# number1.net
KiCad netlist of a schematic drawn in Altium Designer
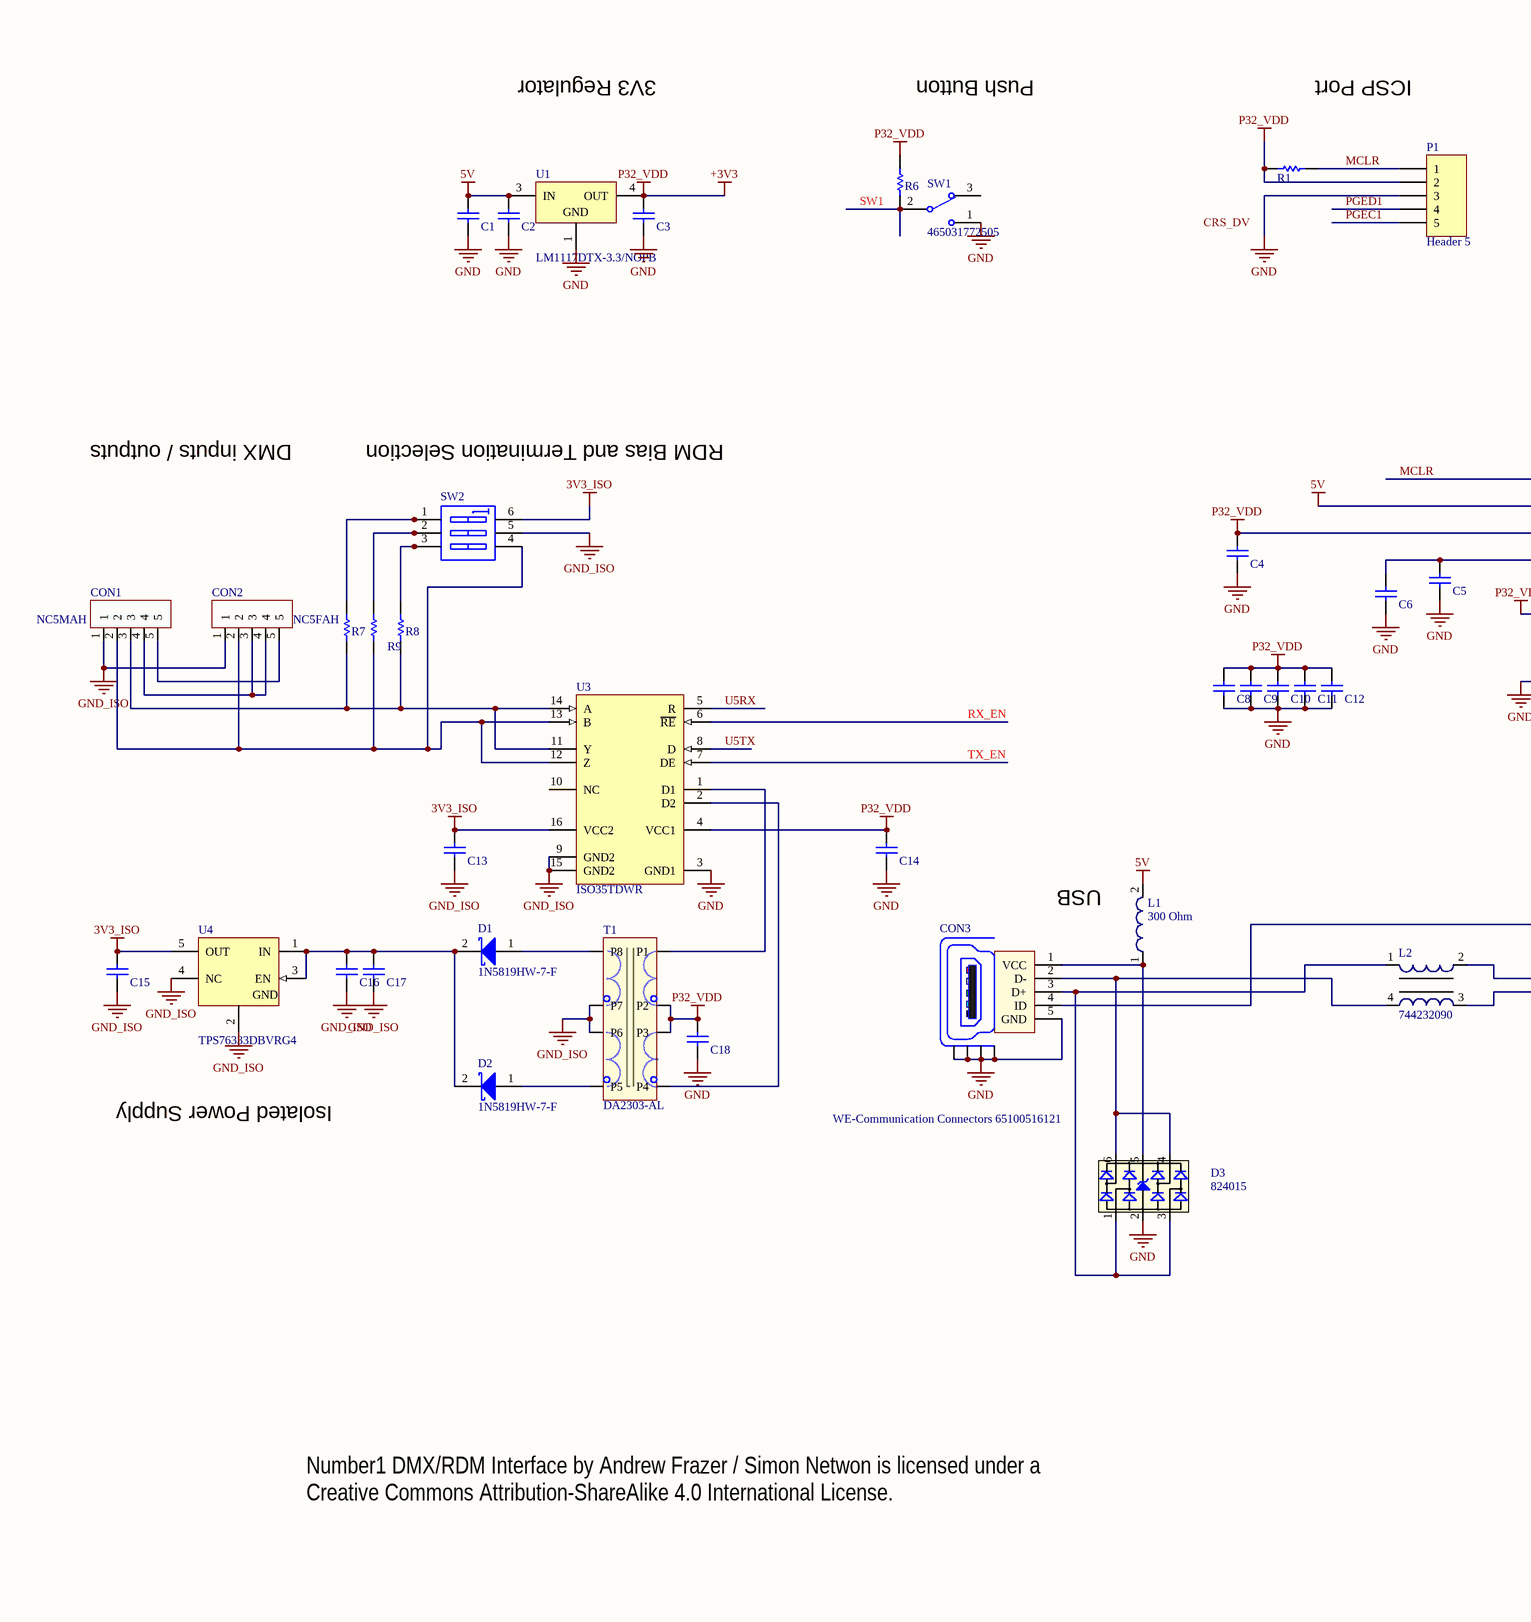
[diagram p0: number1.SchDoc, left]
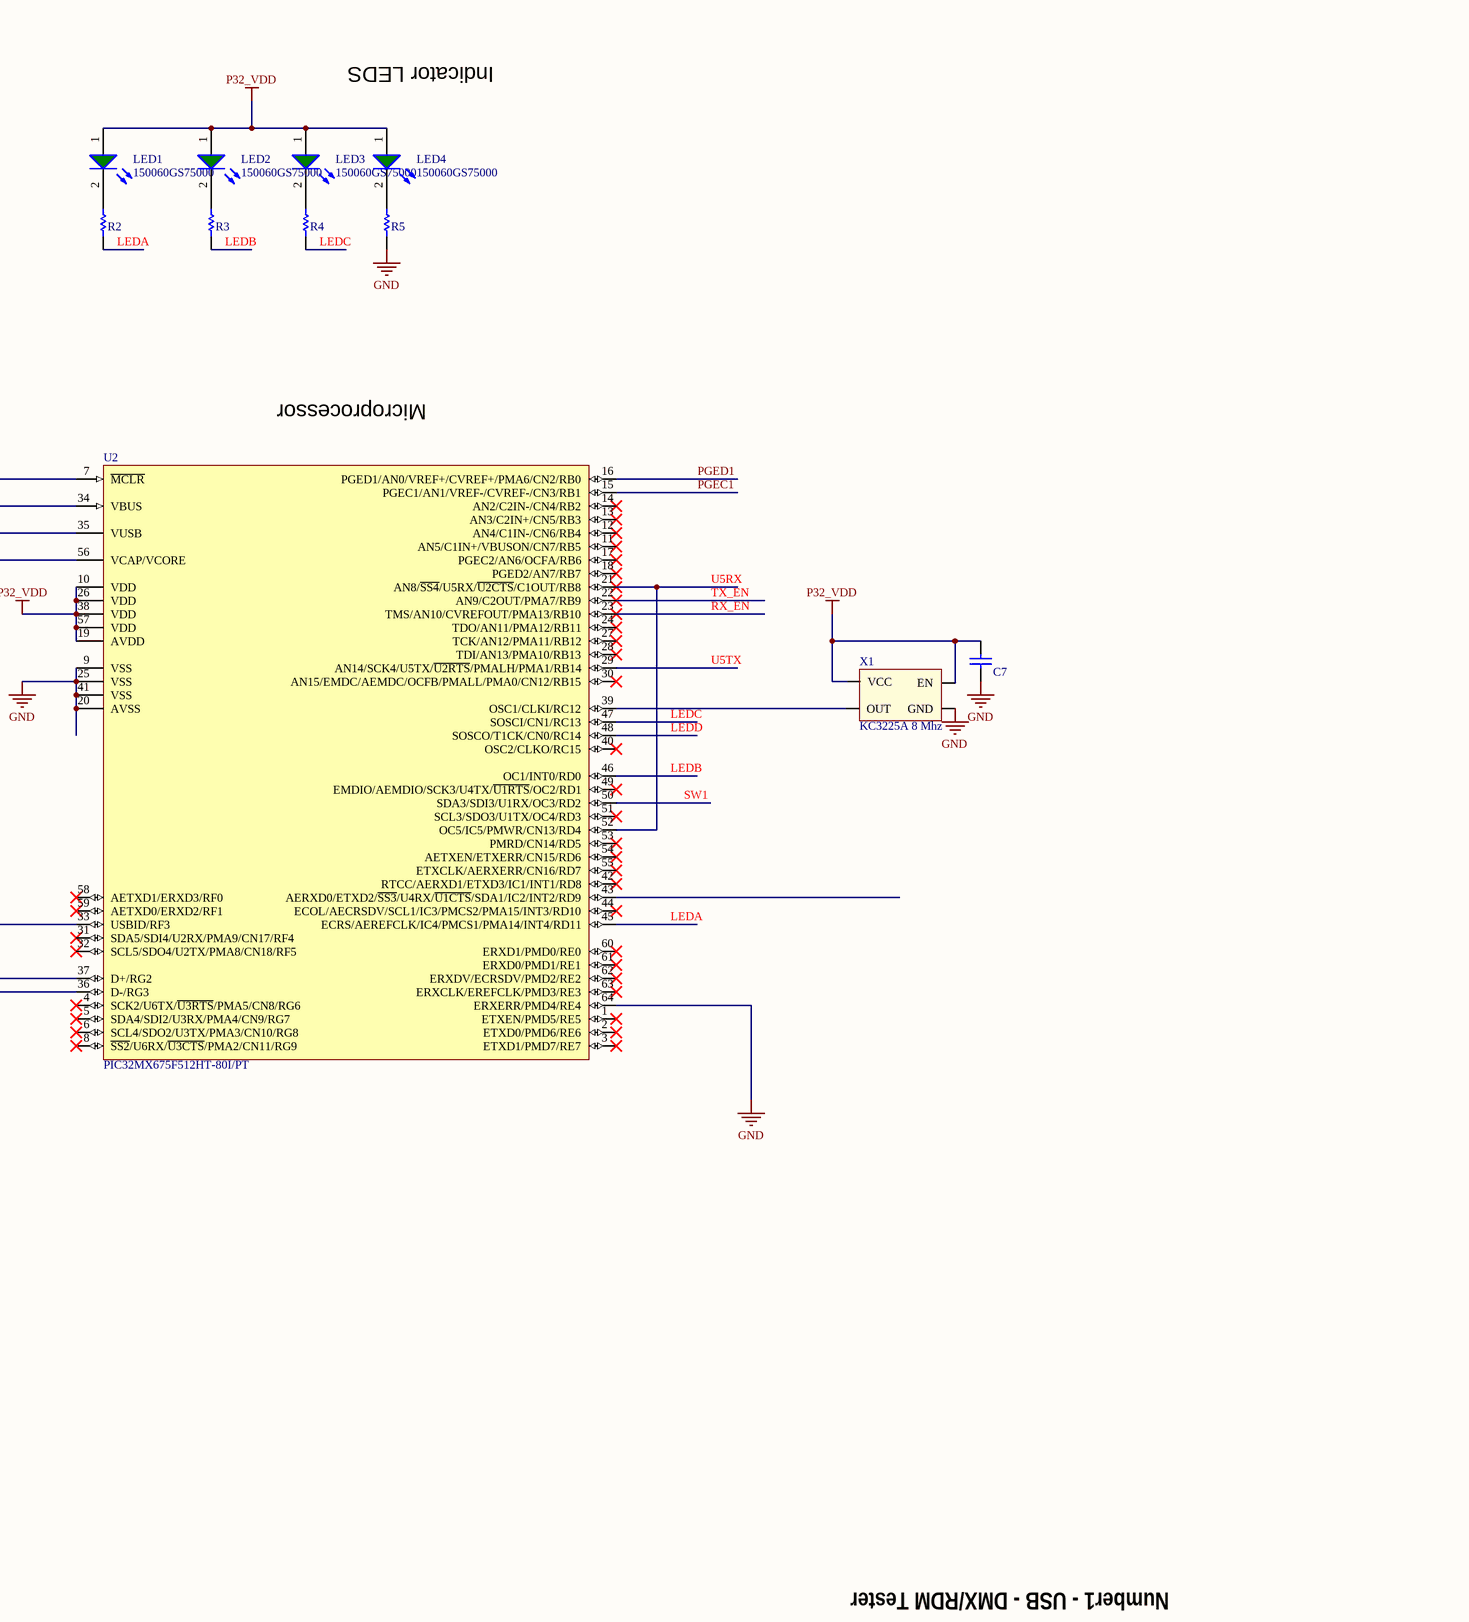
[diagram p1: number1.SchDoc, right]

(export (version "E")
  (design (tool "Eeschema 10.0.6"))
  (components
    (comp (ref "C1")
      (value "CAP 10.0uF 50V 0805(2012)")
      (footprint "CAPC0805(2012)145_M")
      (description "CAP 10uF 50V ±20% 0805 (2012 Metric) Thickness 1.45mm SMD")
      (fields (field (name "TOLERANCE") "±20%"))
      (libsource (lib "Altium Content Vault") (part "CMP-1036-04901-1"))
    )
    (comp (ref "C2")
      (value "CAP 100nF 50V 0402(1005)")
      (footprint "CAPC0402(1005)60_M")
      (description "CAP 100nF 50V ±10% 0402 (1005 Metric) Thickness 0.6mm SMD")
      (fields (field (name "TOLERANCE") "±10%"))
      (libsource (lib "Altium Content Vault") (part "CAP"))
    )
    (comp (ref "C3")
      (value "CAP 100nF 50V 0402(1005)")
      (footprint "CAPC0402(1005)60_M")
      (description "CAP 100nF 50V ±10% 0402 (1005 Metric) Thickness 0.6mm SMD")
      (fields (field (name "TOLERANCE") "±10%"))
      (libsource (lib "Altium Content Vault") (part "CAP"))
    )
    (comp (ref "C4")
      (value "CAP 100nF 50V 0402(1005)")
      (footprint "CAPC0402(1005)60_M")
      (description "CAP 100nF 50V ±10% 0402 (1005 Metric) Thickness 0.6mm SMD")
      (fields (field (name "TOLERANCE") "±10%"))
      (libsource (lib "Altium Content Vault") (part "CMP-1034-02077-1"))
    )
    (comp (ref "C5")
      (value "CAP 10.0uF 50V 0805(2012)")
      (footprint "CAPC0805(2012)145_M")
      (description "CAP 10uF 50V ±20% 0805 (2012 Metric) Thickness 1.45mm SMD")
      (fields (field (name "TOLERANCE") "±20%"))
      (libsource (lib "Altium Content Vault") (part "CMP-1036-04901-1"))
    )
    (comp (ref "C6")
      (value "CAP 100nF 50V 0402(1005)")
      (footprint "CAPC0402(1005)60_M")
      (description "CAP 100nF 50V ±10% 0402 (1005 Metric) Thickness 0.6mm SMD")
      (fields (field (name "TOLERANCE") "±10%"))
      (libsource (lib "Altium Content Vault") (part "CAP"))
    )
    (comp (ref "C7")
      (value "CAP 100nF 50V 0402(1005)")
      (footprint "CAPC0402(1005)60_M")
      (description "CAP 100nF 50V ±10% 0402 (1005 Metric) Thickness 0.6mm SMD")
      (fields (field (name "TOLERANCE") "±10%"))
      (libsource (lib "Altium Content Vault") (part "CMP-1034-02077-1"))
    )
    (comp (ref "C8")
      (value "CAP 100nF 50V 0402(1005)")
      (footprint "CAPC0402(1005)60_M")
      (description "CAP 100nF 50V ±10% 0402 (1005 Metric) Thickness 0.6mm SMD")
      (fields (field (name "TOLERANCE") "±10%"))
      (libsource (lib "Altium Content Vault") (part "CAP"))
    )
    (comp (ref "C9")
      (value "CAP 100nF 50V 0402(1005)")
      (footprint "CAPC0402(1005)60_M")
      (description "CAP 100nF 50V ±10% 0402 (1005 Metric) Thickness 0.6mm SMD")
      (fields (field (name "TOLERANCE") "±10%"))
      (libsource (lib "Altium Content Vault") (part "CAP"))
    )
    (comp (ref "C10")
      (value "CAP 100nF 50V 0402(1005)")
      (footprint "CAPC0402(1005)60_M")
      (description "CAP 100nF 50V ±10% 0402 (1005 Metric) Thickness 0.6mm SMD")
      (fields (field (name "TOLERANCE") "±10%"))
      (libsource (lib "Altium Content Vault") (part "CAP"))
    )
    (comp (ref "C11")
      (value "CAP 100nF 50V 0402(1005)")
      (footprint "CAPC0402(1005)60_M")
      (description "CAP 100nF 50V ±10% 0402 (1005 Metric) Thickness 0.6mm SMD")
      (fields (field (name "TOLERANCE") "±10%"))
      (libsource (lib "Altium Content Vault") (part "CAP"))
    )
    (comp (ref "C12")
      (value "CAP 100nF 50V 0402(1005)")
      (footprint "CAPC0402(1005)60_M")
      (description "CAP 100nF 50V ±10% 0402 (1005 Metric) Thickness 0.6mm SMD")
      (fields (field (name "TOLERANCE") "±10%"))
      (libsource (lib "Altium Content Vault") (part "CAP"))
    )
    (comp (ref "C13")
      (value "CAP 100nF 50V 0402(1005)")
      (footprint "CAPC0402(1005)60_M")
      (description "CAP 100nF 50V ±10% 0402 (1005 Metric) Thickness 0.6mm SMD")
      (fields (field (name "TOLERANCE") "±10%"))
      (libsource (lib "Altium Content Vault") (part "CMP-1034-02077-1"))
    )
    (comp (ref "C14")
      (value "CAP 100nF 50V 0402(1005)")
      (footprint "CAPC0402(1005)60_M")
      (description "CAP 100nF 50V ±10% 0402 (1005 Metric) Thickness 0.6mm SMD")
      (fields (field (name "TOLERANCE") "±10%"))
      (libsource (lib "Altium Content Vault") (part "CMP-1034-02077-1"))
    )
    (comp (ref "C15")
      (value "CAP 10.0uF 50V 0805(2012)")
      (footprint "CAPC0805(2012)145_M")
      (description "CAP 10uF 50V ±20% 0805 (2012 Metric) Thickness 1.45mm SMD")
      (fields (field (name "TOLERANCE") "±20%"))
      (libsource (lib "Altium Content Vault") (part "CMP-1036-04901-1"))
    )
    (comp (ref "C16")
      (value "CAP 100nF 50V 0402(1005)")
      (footprint "CAPC0402(1005)60_M")
      (description "CAP 100nF 50V ±10% 0402 (1005 Metric) Thickness 0.6mm SMD")
      (fields (field (name "TOLERANCE") "±10%"))
      (libsource (lib "Altium Content Vault") (part "CMP-1034-02077-1"))
    )
    (comp (ref "C17")
      (value "CAP 10.0uF 50V 0805(2012)")
      (footprint "CAPC0805(2012)145_M")
      (description "CAP 10uF 50V ±20% 0805 (2012 Metric) Thickness 1.45mm SMD")
      (fields (field (name "TOLERANCE") "±20%"))
      (libsource (lib "Altium Content Vault") (part "CMP-1036-04901-1"))
    )
    (comp (ref "C18")
      (value "CAP 10.0uF 50V 0805(2012)")
      (footprint "CAPC0805(2012)145_M")
      (description "CAP 10uF 50V ±20% 0805 (2012 Metric) Thickness 1.45mm SMD")
      (fields (field (name "TOLERANCE") "±20%"))
      (libsource (lib "Altium Content Vault") (part "CMP-1036-04901-1"))
    )
    (comp (ref "CON1") (value "NC5MAH") (footprint "NC5MAH") (libsource (lib "neutrik") (part "NC5MAH")))
    (comp (ref "CON2") (value "NC5FAH") (footprint "NC5FAH") (libsource (lib "neutrik") (part "NC5FAH")))
    (comp (ref "CON3")
      (value "WE-Communication Connectors 65100516121")
      (footprint "65100516121")
      (description "WR-COM Mini USB SMT Type B 5 Contacts")
      (fields
        (field (name "MANUFACTURER") "Würth Elektronik eiSos GmbH")
        (field (name "PARTNO") "65100516121")
        (field (name "CREATED BY") "Karrer Zheng")
      )
      (libsource (lib "65100516121") (part "WE-Communication Connectors 65100516121"))
    )
    (comp (ref "D1")
      (value "1N5819HW-7-F")
      (footprint "DIOD-SOD-123-2_V")
      (fields (field (name "MANUFACTURER") "Diodes Inc"))
      (libsource (lib "Altium Content Vault") (part "DIOD-DSKY-A1K2-2"))
    )
    (comp (ref "D2")
      (value "1N5819HW-7-F")
      (footprint "DIOD-SOD-123-2_V")
      (fields (field (name "MANUFACTURER") "Diodes Inc"))
      (libsource (lib "Altium Content Vault") (part "DIOD-DSKY-A1K2-2"))
    )
    (comp (ref "D3")
      (value "824015")
      (footprint "SOT23_6L")
      (description "TVS Diode WE-TVS-HS, VRWM=5V")
      (fields
        (field (name "MANUFACTURER") "W黵th Elektronik eiSos GmbH")
        (field (name "CREATED BY") "Christin Zierenner")
      )
      (libsource (lib "WE-TVSHighSpeed") (part "WE-TVS-HS,SOT23-6L, 824015"))
    )
    (comp (ref "L1")
      (value "300 Ohm")
      (footprint "SMD 0603")
      (description "SMD EMI Suppression Ferrite Beads WE-CBF, Z= 300 Ohm")
      (fields
        (field (name "PARTNO") "742792641")
        (field (name "MANUFACTURER") "Würth Elektronik eiSos GmbH")
        (field (name "CREATED BY") "Christin Zierenner")
      )
      (libsource (lib "WE-CBF") (part "WE-CBF 0603, 742792641"))
    )
    (comp (ref "L2")
      (value "744232090")
      (footprint "WE-CNSW, 1206")
      (description "SMD Common Mode Noise Suppressor WE-CNSW,  Z= 90 Ohm")
      (fields
        (field (name "MANUFACTURER") "Würth Elektronik eiSos GmbH")
        (field (name "CREATED BY") "Christin Zierenner")
      )
      (libsource (lib "WE-CNSW") (part "WE-CNSW 1206, 744232090"))
    )
    (comp (ref "LED1")
      (value "150060GS75000")
      (footprint "LED_0603_Green")
      (description "SMD mono-color Chip LED, WL-SMCW, Green")
      (fields
        (field (name "MANUFACTURER") "W黵th Elektronik eiSos GmbH")
        (field (name "CREATED BY") "Christin Otto")
      )
      (libsource (lib "WL-SMCW") (part "WL-SMCW 0603  150060GS75000"))
    )
    (comp (ref "LED2")
      (value "150060GS75000")
      (footprint "LED_0603_Green")
      (description "SMD mono-color Chip LED, WL-SMCW, Green")
      (fields
        (field (name "MANUFACTURER") "W黵th Elektronik eiSos GmbH")
        (field (name "CREATED BY") "Christin Otto")
      )
      (libsource (lib "WL-SMCW") (part "WL-SMCW 0603  150060GS75000"))
    )
    (comp (ref "LED3")
      (value "150060GS75000")
      (footprint "LED_0603_Green")
      (description "SMD mono-color Chip LED, WL-SMCW, Green")
      (fields
        (field (name "MANUFACTURER") "W黵th Elektronik eiSos GmbH")
        (field (name "CREATED BY") "Christin Otto")
      )
      (libsource (lib "WL-SMCW") (part "WL-SMCW 0603  150060GS75000"))
    )
    (comp (ref "LED4")
      (value "150060GS75000")
      (footprint "LED_0603_Green")
      (description "SMD mono-color Chip LED, WL-SMCW, Green")
      (fields
        (field (name "MANUFACTURER") "W黵th Elektronik eiSos GmbH")
        (field (name "CREATED BY") "Christin Otto")
      )
      (libsource (lib "WL-SMCW") (part "WL-SMCW 0603  150060GS75000"))
    )
    (comp (ref "P1")
      (value "Header 5")
      (footprint "HDR1X5")
      (description "Header, 5-Pin")
      (fields (field (name "PUBLISHER") "Altium Limited"))
      (libsource (lib "Miscellaneous Connectors") (part "Header 5"))
    )
    (comp (ref "R1")
      (value "4K7 1% 0603(1608)")
      (footprint "RESC0603(1608)_N")
      (description "4K87 0.1W 1% 0603 (1608 Metric)  SMD")
      (fields (field (name "POWER") "0.1 W") (field (name "TOLERANCE") "1 %"))
      (libsource (lib "Altium Content Vault") (part "CMP-1012-00586-1"))
    )
    (comp (ref "R2")
      (value "100R 1% 0603(1608)")
      (footprint "RESC0603(1608)_M")
      (description "100R 0.1W 1% 0603 (1608 Metric)  SMD")
      (fields (field (name "TOLERANCE") "1 %") (field (name "POWER") "0.1 W"))
      (libsource (lib "Altium Content Vault") (part "RES"))
    )
    (comp (ref "R3")
      (value "100R 1% 0603(1608)")
      (footprint "RESC0603(1608)_M")
      (description "100R 0.1W 1% 0603 (1608 Metric)  SMD")
      (fields (field (name "TOLERANCE") "1 %") (field (name "POWER") "0.1 W"))
      (libsource (lib "Altium Content Vault") (part "RES"))
    )
    (comp (ref "R4")
      (value "100R 1% 0603(1608)")
      (footprint "RESC0603(1608)_M")
      (description "100R 0.1W 1% 0603 (1608 Metric)  SMD")
      (fields (field (name "TOLERANCE") "1 %") (field (name "POWER") "0.1 W"))
      (libsource (lib "Altium Content Vault") (part "RES"))
    )
    (comp (ref "R5")
      (value "100R 1% 0603(1608)")
      (footprint "RESC0603(1608)_M")
      (description "100R 0.1W 1% 0603 (1608 Metric)  SMD")
      (fields (field (name "TOLERANCE") "1 %") (field (name "POWER") "0.1 W"))
      (libsource (lib "Altium Content Vault") (part "RES"))
    )
    (comp (ref "R6")
      (value "4K7 1% 0603(1608)")
      (footprint "RESC0603(1608)_N")
      (description "4K87 0.1W 1% 0603 (1608 Metric)  SMD")
      (fields (field (name "POWER") "0.1 W") (field (name "TOLERANCE") "1 %"))
      (libsource (lib "Altium Content Vault") (part "CMP-1012-00586-1"))
    )
    (comp (ref "R7")
      (value "560R 1% 1206(3216)")
      (footprint "RESC1206(3216)_N")
      (description "560R 0.25W 1% 1206 (3216 Metric)  SMD")
      (fields (field (name "TOLERANCE") "1 %") (field (name "POWER") "0.25 W"))
      (libsource (lib "Altium Content Vault") (part "RES"))
    )
    (comp (ref "R8")
      (value "133R 1% 1206(3216)")
      (footprint "RESC1206(3216)_M")
      (description "133R 0.25W 1% 1206 (3216 Metric)  SMD")
      (fields (field (name "POWER") "0.25 W") (field (name "TOLERANCE") "1 %"))
      (libsource (lib "Altium Content Vault") (part "RES"))
    )
    (comp (ref "R9")
      (value "560R 1% 1206(3216)")
      (footprint "RESC1206(3216)_N")
      (description "560R 0.25W 1% 1206 (3216 Metric)  SMD")
      (fields (field (name "TOLERANCE") "1 %") (field (name "POWER") "0.25 W"))
      (libsource (lib "Altium Content Vault") (part "RES"))
    )
    (comp (ref "SW1")
      (value "465031772505")
      (footprint "465031772505")
      (description "WS-PBTU THT Push button Switch 18.5x9.8mm")
      (fields
        (field (name "MANUFACTURER") "Wurth Elektronik")
        (field (name "E-MAIL") "libraries@we-online.com")
        (field (name "CREATED BY") "Karrer Zheng")
      )
      (libsource (lib "Druckschalter") (part "WE-Push button Switches WS-PBTU 465031772505"))
    )
    (comp (ref "SW2")
      (value "WE-Dip Switches WS-DITU 418217270903")
      (footprint "418217270903")
      (description "WS-DITU 2.54 mm right angled compact THT Dip Switch with raised actuator")
      (fields
        (field (name "MANUFACTURER") "Würth Elektronik eiSos GmbH & Co.KG")
        (field (name "PARTNO") "418217270903")
        (field (name "CREAT BY") "Karrer Zheng")
      )
      (libsource (lib "DipSchalter") (part "WE-Dip Switches WS-DITU 418217270903"))
    )
    (comp (ref "T1")
      (value "DA2303-AL")
      (footprint "DA2303-AL - duplicate")
      (libsource (lib "stella_current") (part "DA2303-AL"))
    )
    (comp (ref "U1")
      (value "LM1117DTX-3.3/NOPB")
      (footprint "TD03B_N")
      (description "800mA Low-Dropout Linear Regulator, 3-pin TO-252, Pb-Free")
      (fields (field (name "MANUFACTURER") "National Semiconductor"))
      (libsource (lib "Altium Content Vault") (part "PM-REG-LMS8117-TO3"))
    )
    (comp (ref "U2")
      (value "PIC32MX675F512HT-80I/PT")
      (footprint "TQFP-PT64_M")
      (libsource (lib "Altium Content Vault") (part "MC-32B-MX675-SQ64"))
    )
    (comp (ref "U3")
      (value "ISO35TDWR")
      (footprint "DW0016A_L")
      (fields (field (name "MANUFACTURER") "Texas Instruments"))
      (libsource (lib "Altium Content Vault") (part "TI-ISO35T-SOIC_DW-16"))
    )
    (comp (ref "U4")
      (value "TPS76333DBVRG4")
      (footprint "TI-DBV5_N")
      (fields (field (name "MANUFACTURER") "Texas Instruments"))
      (libsource (lib "Altium Content Vault") (part "TI-TXX7XXXX-5"))
    )
    (comp (ref "X1")
      (value "KC3225A 8 Mhz")
      (footprint "K25-2C")
      (description "8Mhz Xtal")
      (libsource (lib "stella_current") (part "KC3225A 50.000Mhz"))
    )
  )
  (nets
    (net (code "1") (name "+3V3") (class "Default")
      (node (ref "C10") (pin "2") (pinfunction "2_2") (pintype "passive"))
      (node (ref "C11") (pin "2") (pinfunction "2_2") (pintype "passive"))
      (node (ref "C12") (pin "2") (pinfunction "2_2") (pintype "passive"))
      (node (ref "C14") (pin "2") (pinfunction "2_2") (pintype "passive"))
      (node (ref "C18") (pin "1") (pinfunction "1_1") (pintype "passive"))
      (node (ref "C3") (pin "2") (pinfunction "2_2") (pintype "passive"))
      (node (ref "C4") (pin "2") (pinfunction "2_2") (pintype "passive"))
      (node (ref "C7") (pin "2") (pinfunction "2_2") (pintype "passive"))
      (node (ref "C8") (pin "2") (pinfunction "2_2") (pintype "passive"))
      (node (ref "C9") (pin "2") (pinfunction "2_2") (pintype "passive"))
      (node (ref "LED1") (pin "1") (pinfunction "A_1") (pintype "passive"))
      (node (ref "LED2") (pin "1") (pinfunction "A_1") (pintype "passive"))
      (node (ref "LED3") (pin "1") (pinfunction "A_1") (pintype "passive"))
      (node (ref "LED4") (pin "1") (pinfunction "A_1") (pintype "passive"))
      (node (ref "P1") (pin "2") (pinfunction "2_2") (pintype "passive"))
      (node (ref "R1") (pin "1") (pinfunction "1_1") (pintype "passive"))
      (node (ref "R6") (pin "2") (pinfunction "2_2") (pintype "passive"))
      (node (ref "T1") (pin "2") (pinfunction "P2_2") (pintype "passive"))
      (node (ref "T1") (pin "3") (pinfunction "P3_3") (pintype "passive"))
      (node (ref "U1") (pin "4") (pinfunction "OUT_4") (pintype "power_in"))
      (node (ref "U2") (pin "10") (pinfunction "VDD_10") (pintype "power_in"))
      (node (ref "U2") (pin "19") (pinfunction "AVDD_19") (pintype "power_in"))
      (node (ref "U2") (pin "26") (pinfunction "VDD_26") (pintype "power_in"))
      (node (ref "U2") (pin "35") (pinfunction "VUSB_35") (pintype "power_in"))
      (node (ref "U2") (pin "38") (pinfunction "VDD_38") (pintype "power_in"))
      (node (ref "U2") (pin "57") (pinfunction "VDD_57") (pintype "power_in"))
      (node (ref "U3") (pin "4") (pinfunction "VCC1_4") (pintype "power_in"))
      (node (ref "X1") (pin "1") (pinfunction "EN_1") (pintype "passive"))
      (node (ref "X1") (pin "4") (pinfunction "VCC_4") (pintype "passive"))
    )
    (net (code "2") (name "/LEDA") (class "Default")
      (node (ref "R2") (pin "1") (pinfunction "1_1") (pintype "passive"))
      (node (ref "U2") (pin "45") (pinfunction "ECRS/AEREFCLK/IC4/PMCS1/PMA14/INT4/RD11_45") (pintype "bidirectional"))
    )
    (net (code "3") (name "/LEDB") (class "Default")
      (node (ref "R3") (pin "1") (pinfunction "1_1") (pintype "passive"))
      (node (ref "U2") (pin "46") (pinfunction "OC1/INT0/RD0_46") (pintype "bidirectional"))
    )
    (net (code "4") (name "/LEDC") (class "Default")
      (node (ref "R4") (pin "1") (pinfunction "1_1") (pintype "passive"))
      (node (ref "U2") (pin "47") (pinfunction "SOSCI/CN1/RC13_47") (pintype "bidirectional"))
    )
    (net (code "5") (name "/LEDD") (class "Default")
      (node (ref "U2") (pin "48") (pinfunction "SOSCO/T1CK/CN0/RC14_48") (pintype "bidirectional"))
    )
    (net (code "6") (name "/MCLR") (class "Default")
      (node (ref "P1") (pin "1") (pinfunction "1_1") (pintype "passive"))
      (node (ref "R1") (pin "2") (pinfunction "2_2") (pintype "passive"))
      (node (ref "U2") (pin "7") (pinfunction "~{MCLR}_7") (pintype "input"))
    )
    (net (code "7") (name "/PGEC1") (class "Default")
      (node (ref "P1") (pin "5") (pinfunction "5_5") (pintype "passive"))
      (node (ref "U2") (pin "15") (pinfunction "PGEC1/AN1/VREF-/CVREF-/CN3/RB1_15") (pintype "bidirectional"))
    )
    (net (code "8") (name "/PGED1") (class "Default")
      (node (ref "P1") (pin "4") (pinfunction "4_4") (pintype "passive"))
      (node (ref "U2") (pin "16") (pinfunction "PGED1/AN0/VREF+/CVREF+/PMA6/CN2/RB0_16") (pintype "bidirectional"))
    )
    (net (code "9") (name "/RX_EN") (class "Default")
      (node (ref "U2") (pin "23") (pinfunction "TMS/AN10/CVREFOUT/PMA13/RB10_23") (pintype "bidirectional"))
      (node (ref "U3") (pin "6") (pinfunction "~{RE}_6") (pintype "input"))
    )
    (net (code "10") (name "/SW1") (class "Default")
      (node (ref "R6") (pin "1") (pinfunction "1_1") (pintype "passive"))
      (node (ref "SW1") (pin "2") (pinfunction "2_2") (pintype "passive"))
      (node (ref "U2") (pin "50") (pinfunction "SDA3/SDI3/U1RX/OC3/RD2_50") (pintype "bidirectional"))
    )
    (net (code "11") (name "/TX_EN") (class "Default")
      (node (ref "U2") (pin "22") (pinfunction "AN9/C2OUT/PMA7/RB9_22") (pintype "bidirectional"))
      (node (ref "U3") (pin "7") (pinfunction "DE_7") (pintype "input"))
    )
    (net (code "12") (name "/U5RX") (class "Default")
      (node (ref "U2") (pin "21") (pinfunction "AN8/~{SS4}/U5RX/~{U2CTS}/C1OUT/RB8_21") (pintype "bidirectional"))
      (node (ref "U2") (pin "52") (pinfunction "OC5/IC5/PMWR/CN13/RD4_52") (pintype "bidirectional"))
      (node (ref "U3") (pin "5") (pinfunction "R_5") (pintype "tri_state"))
    )
    (net (code "13") (name "/U5TX") (class "Default")
      (node (ref "U2") (pin "29") (pinfunction "AN14/SCK4/U5TX/~{U2RTS}/PMALH/PMA1/RB14_29") (pintype "bidirectional"))
      (node (ref "U3") (pin "8") (pinfunction "D_8") (pintype "input"))
    )
    (net (code "14") (name "3V3_ISO") (class "Default")
      (node (ref "C13") (pin "2") (pinfunction "2_2") (pintype "passive"))
      (node (ref "C15") (pin "1") (pinfunction "1_1") (pintype "passive"))
      (node (ref "SW2") (pin "6") (pinfunction "6_6") (pintype "passive"))
      (node (ref "U3") (pin "16") (pinfunction "VCC2_16") (pintype "power_in"))
      (node (ref "U4") (pin "5") (pinfunction "OUT_5") (pintype "power_in"))
    )
    (net (code "15") (name "5V") (class "Default")
      (node (ref "C1") (pin "1") (pinfunction "1_1") (pintype "passive"))
      (node (ref "C2") (pin "2") (pinfunction "2_2") (pintype "passive"))
      (node (ref "L1") (pin "2") (pinfunction "2_2") (pintype "passive"))
      (node (ref "U1") (pin "3") (pinfunction "IN_3") (pintype "power_in"))
      (node (ref "U2") (pin "34") (pinfunction "VBUS_34") (pintype "input"))
    )
    (net (code "16") (name "GND") (class "Default")
      (node (ref "C1") (pin "2") (pinfunction "2_2") (pintype "passive"))
      (node (ref "C10") (pin "1") (pinfunction "1_1") (pintype "passive"))
      (node (ref "C11") (pin "1") (pinfunction "1_1") (pintype "passive"))
      (node (ref "C12") (pin "1") (pinfunction "1_1") (pintype "passive"))
      (node (ref "C14") (pin "1") (pinfunction "1_1") (pintype "passive"))
      (node (ref "C18") (pin "2") (pinfunction "2_2") (pintype "passive"))
      (node (ref "C2") (pin "1") (pinfunction "1_1") (pintype "passive"))
      (node (ref "C3") (pin "1") (pinfunction "1_1") (pintype "passive"))
      (node (ref "C4") (pin "1") (pinfunction "1_1") (pintype "passive"))
      (node (ref "C5") (pin "2") (pinfunction "2_2") (pintype "passive"))
      (node (ref "C6") (pin "1") (pinfunction "1_1") (pintype "passive"))
      (node (ref "C7") (pin "1") (pinfunction "1_1") (pintype "passive"))
      (node (ref "C8") (pin "1") (pinfunction "1_1") (pintype "passive"))
      (node (ref "C9") (pin "1") (pinfunction "1_1") (pintype "passive"))
      (node (ref "CON3") (pin "5") (pinfunction "GND_5") (pintype "passive"))
      (node (ref "CON3") (pin "Z1") (pinfunction "Shield_Z1") (pintype "passive"))
      (node (ref "CON3") (pin "Z2") (pinfunction "Shield_Z2") (pintype "passive"))
      (node (ref "CON3") (pin "Z3") (pinfunction "Shield_Z3") (pintype "passive"))
      (node (ref "CON3") (pin "Z4") (pinfunction "Shield_Z4") (pintype "passive"))
      (node (ref "D3") (pin "2") (pinfunction "GND_2") (pintype "passive"))
      (node (ref "P1") (pin "3") (pinfunction "3_3") (pintype "passive"))
      (node (ref "R5") (pin "1") (pinfunction "1_1") (pintype "passive"))
      (node (ref "SW1") (pin "1") (pinfunction "1_1") (pintype "passive"))
      (node (ref "U1") (pin "1") (pinfunction "GND_1") (pintype "power_in"))
      (node (ref "U2") (pin "20") (pinfunction "AVSS_20") (pintype "power_in"))
      (node (ref "U2") (pin "25") (pinfunction "VSS_25") (pintype "power_in"))
      (node (ref "U2") (pin "41") (pinfunction "VSS_41") (pintype "power_in"))
      (node (ref "U2") (pin "64") (pinfunction "ERXERR/PMD4/RE4_64") (pintype "bidirectional"))
      (node (ref "U2") (pin "9") (pinfunction "VSS_9") (pintype "power_in"))
      (node (ref "U3") (pin "3") (pinfunction "GND1_3") (pintype "power_in"))
      (node (ref "X1") (pin "2") (pinfunction "GND_2") (pintype "passive"))
    )
    (net (code "17") (name "GND_ISO") (class "Default")
      (node (ref "C13") (pin "1") (pinfunction "1_1") (pintype "passive"))
      (node (ref "C15") (pin "2") (pinfunction "2_2") (pintype "passive"))
      (node (ref "C16") (pin "1") (pinfunction "1_1") (pintype "passive"))
      (node (ref "C17") (pin "2") (pinfunction "2_2") (pintype "passive"))
      (node (ref "CON1") (pin "1") (pinfunction "1_1") (pintype "passive"))
      (node (ref "CON2") (pin "1") (pinfunction "1_1") (pintype "passive"))
      (node (ref "SW2") (pin "5") (pinfunction "5_5") (pintype "passive"))
      (node (ref "T1") (pin "6") (pinfunction "P6_6") (pintype "passive"))
      (node (ref "T1") (pin "7") (pinfunction "P7_7") (pintype "passive"))
      (node (ref "U3") (pin "15") (pinfunction "GND2_15") (pintype "power_in"))
      (node (ref "U3") (pin "9") (pinfunction "GND2_9") (pintype "power_in"))
      (node (ref "U4") (pin "2") (pinfunction "GND_2") (pintype "power_in"))
      (node (ref "U4") (pin "4") (pinfunction "NC_4") (pintype "passive"))
    )
    (net (code "18") (name "Net-(CON1-Pad4)") (class "Default")
      (node (ref "CON1") (pin "4") (pinfunction "4_4") (pintype "passive"))
      (node (ref "CON2") (pin "3") (pinfunction "3_3") (pintype "passive"))
      (node (ref "CON2") (pin "4") (pinfunction "4_4") (pintype "passive"))
    )
    (net (code "19") (name "Net-(CON1-Pad5)") (class "Default")
      (node (ref "CON1") (pin "5") (pinfunction "5_5") (pintype "passive"))
      (node (ref "CON2") (pin "5") (pinfunction "5_5") (pintype "passive"))
    )
    (net (code "20") (name "Net-(CON3-D+)") (class "Default")
      (node (ref "CON3") (pin "3") (pinfunction "D+_3") (pintype "passive"))
      (node (ref "D3") (pin "1") (pinfunction "I/O1_1") (pintype "passive"))
      (node (ref "D3") (pin "3") (pinfunction "I/O2_3") (pintype "passive"))
      (node (ref "L2") (pin "1") (pinfunction "1_1") (pintype "passive"))
    )
    (net (code "21") (name "Net-(CON3-D-)") (class "Default")
      (node (ref "CON3") (pin "2") (pinfunction "D-_2") (pintype "passive"))
      (node (ref "D3") (pin "4") (pinfunction "I/O3_4") (pintype "passive"))
      (node (ref "D3") (pin "6") (pinfunction "I/O4_6") (pintype "passive"))
      (node (ref "L2") (pin "4") (pinfunction "4_4") (pintype "passive"))
    )
    (net (code "22") (name "Net-(CON3-ID)") (class "Default")
      (node (ref "CON3") (pin "4") (pinfunction "ID_4") (pintype "passive"))
      (node (ref "U2") (pin "33") (pinfunction "USBID/RF3_33") (pintype "bidirectional"))
    )
    (net (code "23") (name "Net-(CON3-VCC)") (class "Default")
      (node (ref "CON3") (pin "1") (pinfunction "VCC_1") (pintype "passive"))
      (node (ref "D3") (pin "5") (pinfunction "VDD_5") (pintype "passive"))
      (node (ref "L1") (pin "1") (pinfunction "1_1") (pintype "passive"))
    )
    (net (code "24") (name "Net-(D1-A)") (class "Default")
      (node (ref "D1") (pin "1") (pinfunction "A_1") (pintype "passive"))
      (node (ref "T1") (pin "8") (pinfunction "P8_8") (pintype "passive"))
    )
    (net (code "25") (name "Net-(D1-K)") (class "Default")
      (node (ref "C16") (pin "2") (pinfunction "2_2") (pintype "passive"))
      (node (ref "C17") (pin "1") (pinfunction "1_1") (pintype "passive"))
      (node (ref "D1") (pin "2") (pinfunction "K_2") (pintype "passive"))
      (node (ref "D2") (pin "2") (pinfunction "K_2") (pintype "passive"))
      (node (ref "U4") (pin "1") (pinfunction "IN_1") (pintype "power_in"))
      (node (ref "U4") (pin "3") (pinfunction "EN_3") (pintype "input"))
    )
    (net (code "26") (name "Net-(D2-A)") (class "Default")
      (node (ref "D2") (pin "1") (pinfunction "A_1") (pintype "passive"))
      (node (ref "T1") (pin "5") (pinfunction "P5_5") (pintype "passive"))
    )
    (net (code "27") (name "Net-(LED1-C)") (class "Default")
      (node (ref "LED1") (pin "2") (pinfunction "C_2") (pintype "passive"))
      (node (ref "R2") (pin "2") (pinfunction "2_2") (pintype "passive"))
    )
    (net (code "28") (name "Net-(LED2-C)") (class "Default")
      (node (ref "LED2") (pin "2") (pinfunction "C_2") (pintype "passive"))
      (node (ref "R3") (pin "2") (pinfunction "2_2") (pintype "passive"))
    )
    (net (code "29") (name "Net-(LED3-C)") (class "Default")
      (node (ref "LED3") (pin "2") (pinfunction "C_2") (pintype "passive"))
      (node (ref "R4") (pin "2") (pinfunction "2_2") (pintype "passive"))
    )
    (net (code "30") (name "Net-(LED4-C)") (class "Default")
      (node (ref "LED4") (pin "2") (pinfunction "C_2") (pintype "passive"))
      (node (ref "R5") (pin "2") (pinfunction "2_2") (pintype "passive"))
    )
    (net (code "31") (name "Net-(R7-Pad2)") (class "Default")
      (node (ref "R7") (pin "2") (pinfunction "2_2") (pintype "passive"))
      (node (ref "SW2") (pin "1") (pinfunction "1_1") (pintype "passive"))
    )
    (net (code "32") (name "Net-(R8-Pad2)") (class "Default")
      (node (ref "R8") (pin "2") (pinfunction "2_2") (pintype "passive"))
      (node (ref "SW2") (pin "3") (pinfunction "3_3") (pintype "passive"))
    )
    (net (code "33") (name "Net-(R9-Pad2)") (class "Default")
      (node (ref "R9") (pin "2") (pinfunction "2_2") (pintype "passive"))
      (node (ref "SW2") (pin "2") (pinfunction "2_2") (pintype "passive"))
    )
    (net (code "34") (name "Net-(T1-P1)") (class "Default")
      (node (ref "T1") (pin "1") (pinfunction "P1_1") (pintype "passive"))
      (node (ref "U3") (pin "1") (pinfunction "D1_1") (pintype "open_collector"))
    )
    (net (code "35") (name "Net-(T1-P4)") (class "Default")
      (node (ref "T1") (pin "4") (pinfunction "P4_4") (pintype "passive"))
      (node (ref "U3") (pin "2") (pinfunction "D2_2") (pintype "open_collector"))
    )
    (net (code "36") (name "Net-(U2-D+{slash}RG2)") (class "Default")
      (node (ref "L2") (pin "2") (pinfunction "2_2") (pintype "passive"))
      (node (ref "U2") (pin "37") (pinfunction "D+/RG2_37") (pintype "bidirectional"))
    )
    (net (code "37") (name "Net-(U2-D-{slash}RG3)") (class "Default")
      (node (ref "L2") (pin "3") (pinfunction "3_3") (pintype "passive"))
      (node (ref "U2") (pin "36") (pinfunction "D-/RG3_36") (pintype "bidirectional"))
    )
    (net (code "38") (name "Net-(U2-OSC1{slash}CLKI{slash}RC12)") (class "Default")
      (node (ref "U2") (pin "39") (pinfunction "OSC1/CLKI/RC12_39") (pintype "bidirectional"))
      (node (ref "X1") (pin "3") (pinfunction "OUT_3") (pintype "passive"))
    )
    (net (code "39") (name "Net-(U2-VCAP{slash}VCORE)") (class "Default")
      (node (ref "C5") (pin "1") (pinfunction "1_1") (pintype "passive"))
      (node (ref "C6") (pin "2") (pinfunction "2_2") (pintype "passive"))
      (node (ref "U2") (pin "56") (pinfunction "VCAP/VCORE_56") (pintype "power_in"))
    )
    (net (code "40") (name "Net-(U3-A)") (class "Default")
      (node (ref "CON1") (pin "3") (pinfunction "3_3") (pintype "passive"))
      (node (ref "R7") (pin "1") (pinfunction "1_1") (pintype "passive"))
      (node (ref "R8") (pin "1") (pinfunction "1_1") (pintype "passive"))
      (node (ref "U3") (pin "11") (pinfunction "Y_11") (pintype "tri_state"))
      (node (ref "U3") (pin "14") (pinfunction "A_14") (pintype "input"))
    )
    (net (code "41") (name "Net-(U3-B)") (class "Default")
      (node (ref "CON1") (pin "2") (pinfunction "2_2") (pintype "passive"))
      (node (ref "CON2") (pin "2") (pinfunction "2_2") (pintype "passive"))
      (node (ref "R9") (pin "1") (pinfunction "1_1") (pintype "passive"))
      (node (ref "SW2") (pin "4") (pinfunction "4_4") (pintype "passive"))
      (node (ref "U3") (pin "12") (pinfunction "Z_12") (pintype "tri_state"))
      (node (ref "U3") (pin "13") (pinfunction "B_13") (pintype "input"))
    )
    (net (code "42") (name "unconnected-(SW1-Pad3)") (class "Default")
      (node (ref "SW1") (pin "3") (pinfunction "3_3") (pintype "passive"))
    )
    (net (code "43") (name "unconnected-(U2-AERXD0{slash}ETXD2{slash}~{SS3}{slash}U4RX{slash}~{U1CTS}{slash}SDA1{slash}IC2{slash}INT2{slash}RD9-Pad43)") (class "Default")
      (node (ref "U2") (pin "43") (pinfunction "AERXD0/ETXD2/~{SS3}/U4RX/~{U1CTS}/SDA1/IC2/INT2/RD9_43") (pintype "bidirectional"))
    )
    (net (code "44") (name "unconnected-(U2-AETXD0{slash}ERXD2{slash}RF1-Pad59)") (class "Default")
      (node (ref "U2") (pin "59") (pinfunction "AETXD0/ERXD2/RF1_59") (pintype "bidirectional+no_connect"))
    )
    (net (code "45") (name "unconnected-(U2-AETXD1{slash}ERXD3{slash}RF0-Pad58)") (class "Default")
      (node (ref "U2") (pin "58") (pinfunction "AETXD1/ERXD3/RF0_58") (pintype "bidirectional+no_connect"))
    )
    (net (code "46") (name "unconnected-(U2-AETXEN{slash}ETXERR{slash}CN15{slash}RD6-Pad54)") (class "Default")
      (node (ref "U2") (pin "54") (pinfunction "AETXEN/ETXERR/CN15/RD6_54") (pintype "bidirectional+no_connect"))
    )
    (net (code "47") (name "unconnected-(U2-AN2{slash}C2IN-{slash}CN4{slash}RB2-Pad14)") (class "Default")
      (node (ref "U2") (pin "14") (pinfunction "AN2/C2IN-/CN4/RB2_14") (pintype "bidirectional+no_connect"))
    )
    (net (code "48") (name "unconnected-(U2-AN3{slash}C2IN+{slash}CN5{slash}RB3-Pad13)") (class "Default")
      (node (ref "U2") (pin "13") (pinfunction "AN3/C2IN+/CN5/RB3_13") (pintype "bidirectional+no_connect"))
    )
    (net (code "49") (name "unconnected-(U2-AN4{slash}C1IN-{slash}CN6{slash}RB4-Pad12)") (class "Default")
      (node (ref "U2") (pin "12") (pinfunction "AN4/C1IN-/CN6/RB4_12") (pintype "bidirectional+no_connect"))
    )
    (net (code "50") (name "unconnected-(U2-AN5{slash}C1IN+{slash}VBUSON{slash}CN7{slash}RB5-Pad11)") (class "Default")
      (node (ref "U2") (pin "11") (pinfunction "AN5/C1IN+/VBUSON/CN7/RB5_11") (pintype "bidirectional+no_connect"))
    )
    (net (code "51") (name "unconnected-(U2-AN15{slash}EMDC{slash}AEMDC{slash}OCFB{slash}PMALL{slash}PMA0{slash}CN12{slash}RB15-Pad30)") (class "Default")
      (node (ref "U2") (pin "30") (pinfunction "AN15/EMDC/AEMDC/OCFB/PMALL/PMA0/CN12/RB15_30") (pintype "bidirectional+no_connect"))
    )
    (net (code "52") (name "unconnected-(U2-ECOL{slash}AECRSDV{slash}SCL1{slash}IC3{slash}PMCS2{slash}PMA15{slash}INT3{slash}RD10-Pad44)") (class "Default")
      (node (ref "U2") (pin "44") (pinfunction "ECOL/AECRSDV/SCL1/IC3/PMCS2/PMA15/INT3/RD10_44") (pintype "bidirectional+no_connect"))
    )
    (net (code "53") (name "unconnected-(U2-EMDIO{slash}AEMDIO{slash}SCK3{slash}U4TX{slash}~{U1RTS}{slash}OC2{slash}RD1-Pad49)") (class "Default")
      (node (ref "U2") (pin "49") (pinfunction "EMDIO/AEMDIO/SCK3/U4TX/~{U1RTS}/OC2/RD1_49") (pintype "bidirectional+no_connect"))
    )
    (net (code "54") (name "unconnected-(U2-ERXCLK{slash}EREFCLK{slash}PMD3{slash}RE3-Pad63)") (class "Default")
      (node (ref "U2") (pin "63") (pinfunction "ERXCLK/EREFCLK/PMD3/RE3_63") (pintype "bidirectional+no_connect"))
    )
    (net (code "55") (name "unconnected-(U2-ERXD0{slash}PMD1{slash}RE1-Pad61)") (class "Default")
      (node (ref "U2") (pin "61") (pinfunction "ERXD0/PMD1/RE1_61") (pintype "bidirectional+no_connect"))
    )
    (net (code "56") (name "unconnected-(U2-ERXD1{slash}PMD0{slash}RE0-Pad60)") (class "Default")
      (node (ref "U2") (pin "60") (pinfunction "ERXD1/PMD0/RE0_60") (pintype "bidirectional+no_connect"))
    )
    (net (code "57") (name "unconnected-(U2-ERXDV{slash}ECRSDV{slash}PMD2{slash}RE2-Pad62)") (class "Default")
      (node (ref "U2") (pin "62") (pinfunction "ERXDV/ECRSDV/PMD2/RE2_62") (pintype "bidirectional+no_connect"))
    )
    (net (code "58") (name "unconnected-(U2-ETXCLK{slash}AERXERR{slash}CN16{slash}RD7-Pad55)") (class "Default")
      (node (ref "U2") (pin "55") (pinfunction "ETXCLK/AERXERR/CN16/RD7_55") (pintype "bidirectional+no_connect"))
    )
    (net (code "59") (name "unconnected-(U2-ETXD0{slash}PMD6{slash}RE6-Pad2)") (class "Default")
      (node (ref "U2") (pin "2") (pinfunction "ETXD0/PMD6/RE6_2") (pintype "bidirectional+no_connect"))
    )
    (net (code "60") (name "unconnected-(U2-ETXD1{slash}PMD7{slash}RE7-Pad3)") (class "Default")
      (node (ref "U2") (pin "3") (pinfunction "ETXD1/PMD7/RE7_3") (pintype "bidirectional+no_connect"))
    )
    (net (code "61") (name "unconnected-(U2-ETXEN{slash}PMD5{slash}RE5-Pad1)") (class "Default")
      (node (ref "U2") (pin "1") (pinfunction "ETXEN/PMD5/RE5_1") (pintype "bidirectional+no_connect"))
    )
    (net (code "62") (name "unconnected-(U2-OSC2{slash}CLKO{slash}RC15-Pad40)") (class "Default")
      (node (ref "U2") (pin "40") (pinfunction "OSC2/CLKO/RC15_40") (pintype "bidirectional+no_connect"))
    )
    (net (code "63") (name "unconnected-(U2-PGEC2{slash}AN6{slash}OCFA{slash}RB6-Pad17)") (class "Default")
      (node (ref "U2") (pin "17") (pinfunction "PGEC2/AN6/OCFA/RB6_17") (pintype "bidirectional+no_connect"))
    )
    (net (code "64") (name "unconnected-(U2-PGED2{slash}AN7{slash}RB7-Pad18)") (class "Default")
      (node (ref "U2") (pin "18") (pinfunction "PGED2/AN7/RB7_18") (pintype "bidirectional+no_connect"))
    )
    (net (code "65") (name "unconnected-(U2-PMRD{slash}CN14{slash}RD5-Pad53)") (class "Default")
      (node (ref "U2") (pin "53") (pinfunction "PMRD/CN14/RD5_53") (pintype "bidirectional+no_connect"))
    )
    (net (code "66") (name "unconnected-(U2-RTCC{slash}AERXD1{slash}ETXD3{slash}IC1{slash}INT1{slash}RD8-Pad42)") (class "Default")
      (node (ref "U2") (pin "42") (pinfunction "RTCC/AERXD1/ETXD3/IC1/INT1/RD8_42") (pintype "bidirectional+no_connect"))
    )
    (net (code "67") (name "unconnected-(U2-SCK2{slash}U6TX{slash}~{U3RTS}{slash}PMA5{slash}CN8{slash}RG6-Pad4)") (class "Default")
      (node (ref "U2") (pin "4") (pinfunction "SCK2/U6TX/~{U3RTS}/PMA5/CN8/RG6_4") (pintype "bidirectional+no_connect"))
    )
    (net (code "68") (name "unconnected-(U2-SCL3{slash}SDO3{slash}U1TX{slash}OC4{slash}RD3-Pad51)") (class "Default")
      (node (ref "U2") (pin "51") (pinfunction "SCL3/SDO3/U1TX/OC4/RD3_51") (pintype "bidirectional+no_connect"))
    )
    (net (code "69") (name "unconnected-(U2-SCL4{slash}SDO2{slash}U3TX{slash}PMA3{slash}CN10{slash}RG8-Pad6)") (class "Default")
      (node (ref "U2") (pin "6") (pinfunction "SCL4/SDO2/U3TX/PMA3/CN10/RG8_6") (pintype "bidirectional+no_connect"))
    )
    (net (code "70") (name "unconnected-(U2-SCL5{slash}SDO4{slash}U2TX{slash}PMA8{slash}CN18{slash}RF5-Pad32)") (class "Default")
      (node (ref "U2") (pin "32") (pinfunction "SCL5/SDO4/U2TX/PMA8/CN18/RF5_32") (pintype "bidirectional+no_connect"))
    )
    (net (code "71") (name "unconnected-(U2-SDA4{slash}SDI2{slash}U3RX{slash}PMA4{slash}CN9{slash}RG7-Pad5)") (class "Default")
      (node (ref "U2") (pin "5") (pinfunction "SDA4/SDI2/U3RX/PMA4/CN9/RG7_5") (pintype "bidirectional+no_connect"))
    )
    (net (code "72") (name "unconnected-(U2-SDA5{slash}SDI4{slash}U2RX{slash}PMA9{slash}CN17{slash}RF4-Pad31)") (class "Default")
      (node (ref "U2") (pin "31") (pinfunction "SDA5/SDI4/U2RX/PMA9/CN17/RF4_31") (pintype "bidirectional+no_connect"))
    )
    (net (code "73") (name "unconnected-(U2-TCK{slash}AN12{slash}PMA11{slash}RB12-Pad27)") (class "Default")
      (node (ref "U2") (pin "27") (pinfunction "TCK/AN12/PMA11/RB12_27") (pintype "bidirectional+no_connect"))
    )
    (net (code "74") (name "unconnected-(U2-TDI{slash}AN13{slash}PMA10{slash}RB13-Pad28)") (class "Default")
      (node (ref "U2") (pin "28") (pinfunction "TDI/AN13/PMA10/RB13_28") (pintype "bidirectional+no_connect"))
    )
    (net (code "75") (name "unconnected-(U2-TDO{slash}AN11{slash}PMA12{slash}RB11-Pad24)") (class "Default")
      (node (ref "U2") (pin "24") (pinfunction "TDO/AN11/PMA12/RB11_24") (pintype "bidirectional+no_connect"))
    )
    (net (code "76") (name "unconnected-(U2-~{SS2}{slash}U6RX{slash}~{U3CTS}{slash}PMA2{slash}CN11{slash}RG9-Pad8)") (class "Default")
      (node (ref "U2") (pin "8") (pinfunction "~{SS2}/U6RX/~{U3CTS}/PMA2/CN11/RG9_8") (pintype "bidirectional+no_connect"))
    )
    (net (code "77") (name "unconnected-(U3-NC-Pad10)") (class "Default")
      (node (ref "U3") (pin "10") (pinfunction "NC_10") (pintype "passive"))
    )
  )
)
